# Boost_PWR_Supply.net
KiCad netlist of a schematic drawn in Altium Designer
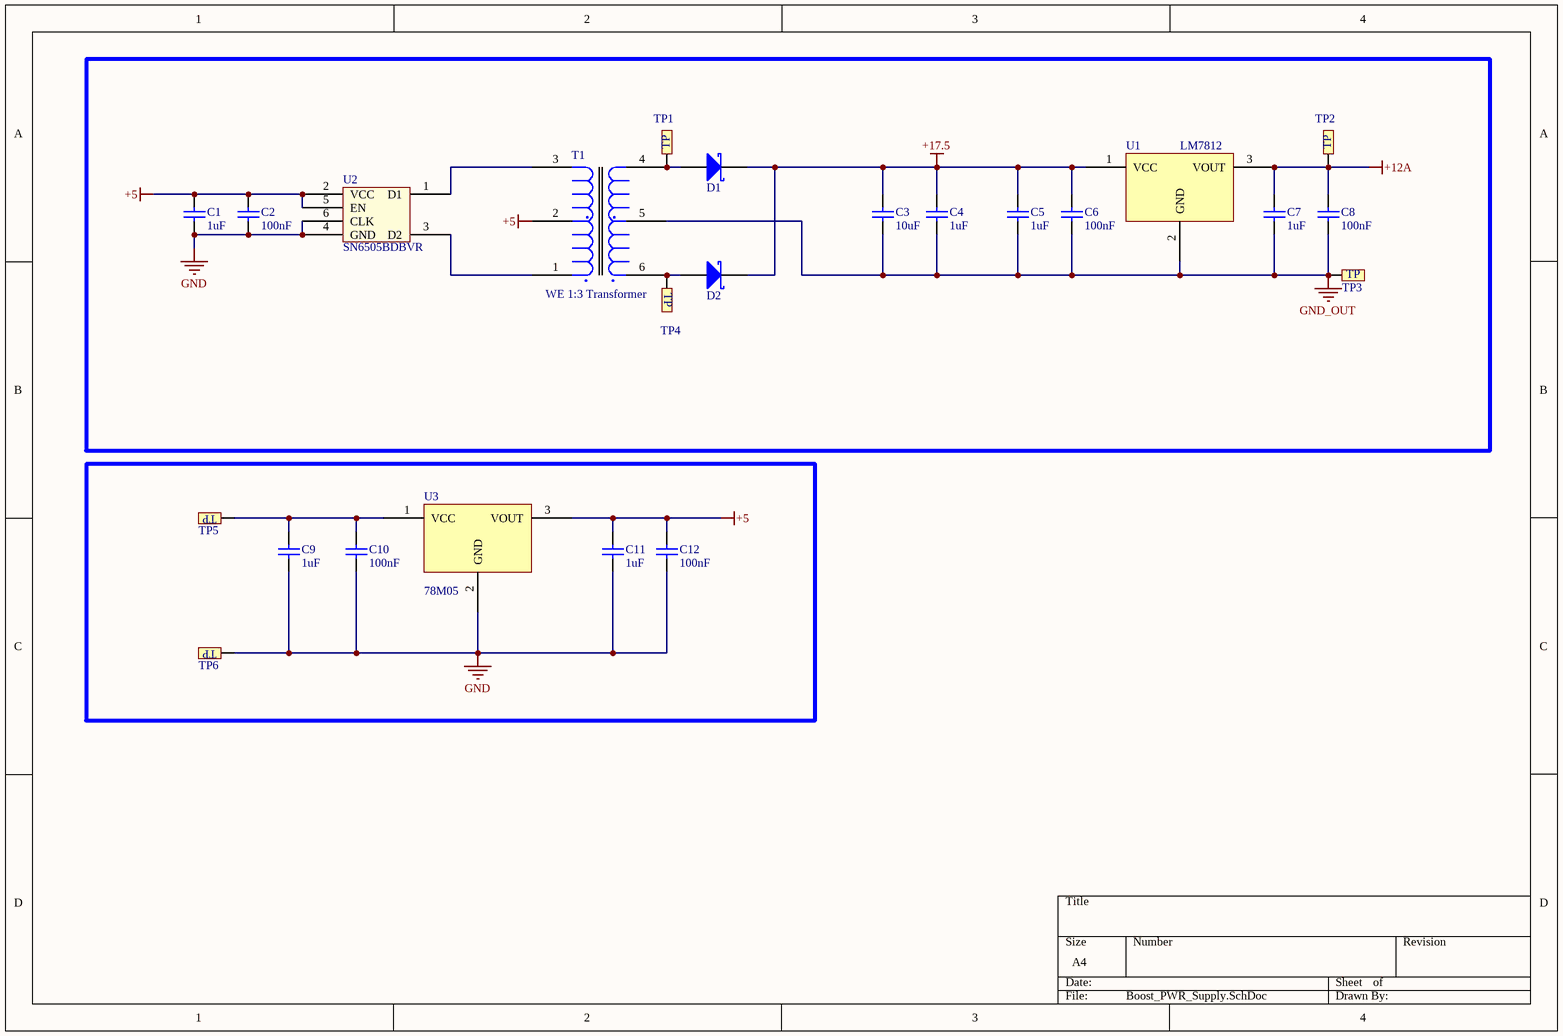
[diagram p0: Boost_PWR_Supply.SchDoc]

(export (version "E")
  (design (tool "Eeschema 10.0.6"))
  (components
    (comp (ref "C1")
      (value "1uF")
      (footprint "CAP-SM-0805")
      (description "Capacitor")
      (fields (field (name "Comment") "Cap Non-Pol SMD"))
      (libsource (lib "PIF_Library") (part "Cap Non-Pol SMD"))
    )
    (comp (ref "C2")
      (value "100nF")
      (footprint "CAP-SM-0805")
      (description "Capacitor")
      (fields (field (name "Comment") "Cap Non-Pol SMD"))
      (libsource (lib "PIF_Library") (part "Cap Non-Pol SMD"))
    )
    (comp (ref "C3")
      (value "10uF")
      (footprint "CAP-SM-0805")
      (description "Capacitor")
      (fields (field (name "Comment") "Cap Non-Pol SMD"))
      (libsource (lib "PIF_Library") (part "Cap Non-Pol SMD"))
    )
    (comp (ref "C4")
      (value "1uF")
      (footprint "CAP-SM-0805")
      (description "Capacitor")
      (fields (field (name "Comment") "Cap Non-Pol SMD"))
      (libsource (lib "PIF_Library") (part "Cap Non-Pol SMD"))
    )
    (comp (ref "C5")
      (value "1uF")
      (footprint "CAP-SM-0805")
      (description "Capacitor")
      (fields (field (name "Comment") "Cap Non-Pol SMD"))
      (libsource (lib "PIF_Library") (part "Cap Non-Pol SMD"))
    )
    (comp (ref "C6")
      (value "100nF")
      (footprint "CAP-SM-0805")
      (description "Capacitor")
      (fields (field (name "Comment") "Cap Non-Pol SMD"))
      (libsource (lib "PIF_Library") (part "Cap Non-Pol SMD"))
    )
    (comp (ref "C7")
      (value "1uF")
      (footprint "CAP-SM-0805")
      (description "Capacitor")
      (fields (field (name "Comment") "Cap Non-Pol SMD"))
      (libsource (lib "PIF_Library") (part "Cap Non-Pol SMD"))
    )
    (comp (ref "C8")
      (value "100nF")
      (footprint "CAP-SM-0805")
      (description "Capacitor")
      (fields (field (name "Comment") "Cap Non-Pol SMD"))
      (libsource (lib "PIF_Library") (part "Cap Non-Pol SMD"))
    )
    (comp (ref "C9")
      (value "1uF")
      (footprint "CAP-SM-0805")
      (description "Capacitor")
      (fields (field (name "Comment") "Cap Non-Pol SMD"))
      (libsource (lib "PIF_Library") (part "Cap Non-Pol SMD"))
    )
    (comp (ref "C10")
      (value "100nF")
      (footprint "CAP-SM-0805")
      (description "Capacitor")
      (fields (field (name "Comment") "Cap Non-Pol SMD"))
      (libsource (lib "PIF_Library") (part "Cap Non-Pol SMD"))
    )
    (comp (ref "C11")
      (value "1uF")
      (footprint "CAP-SM-0805")
      (description "Capacitor")
      (fields (field (name "Comment") "Cap Non-Pol SMD"))
      (libsource (lib "PIF_Library") (part "Cap Non-Pol SMD"))
    )
    (comp (ref "C12")
      (value "100nF")
      (footprint "CAP-SM-0805")
      (description "Capacitor")
      (fields (field (name "Comment") "Cap Non-Pol SMD"))
      (libsource (lib "PIF_Library") (part "Cap Non-Pol SMD"))
    )
    (comp (ref "D1")
      (value "D Schottky")
      (footprint "SS34")
      (description "Schottky Diode")
      (fields (field (name "PUBLISHER") "Altium Limited"))
      (libsource (lib "PIF_Library") (part "D Schottky"))
    )
    (comp (ref "D2")
      (value "D Schottky")
      (footprint "SS34")
      (description "Schottky Diode")
      (fields (field (name "PUBLISHER") "Altium Limited"))
      (libsource (lib "PIF_Library") (part "D Schottky"))
    )
    (comp (ref "T1")
      (value "WE 1:3 Transformer")
      (footprint "750316818")
      (fields (field (name "MANUFACTURER") "Wurth Elektronik"))
      (libsource (lib "MiclsLib") (part "WE 1{colon}3.5 Transformer"))
    )
    (comp (ref "TP1")
      (value "Test Point")
      (footprint "TP_2")
      (libsource (lib "PIF_Library") (part "Test Point"))
    )
    (comp (ref "TP2")
      (value "Test Point")
      (footprint "TP_2")
      (libsource (lib "PIF_Library") (part "Test Point"))
    )
    (comp (ref "TP3") (value "Test Point") (footprint "TP_2") (libsource (lib "") (part "Test Point_1")))
    (comp (ref "TP4") (value "Test Point") (footprint "TP_2") (libsource (lib "") (part "Test Point_3")))
    (comp (ref "TP5") (value "Test Point") (footprint "TP_2") (libsource (lib "") (part "Test Point_2")))
    (comp (ref "TP6") (value "Test Point") (footprint "TP_2") (libsource (lib "") (part "Test Point_2")))
    (comp (ref "U1")
      (value "LM7812")
      (footprint "DPAK228P1014X239-3N")
      (libsource (lib "MiclsLib") (part "LM78xx"))
    )
    (comp (ref "U2")
      (value "SN6505BDBVR")
      (footprint "SOT23-6")
      (description "IC TRANSFORMER DRIVER SOT23-6")
      (fields (field (name "MANUFACTURER") "Texas Instrument"))
      (libsource (lib "PIF_Lib") (part "SN6505BDBVR"))
    )
    (comp (ref "U3")
      (value "78M05")
      (footprint "DPAK228P1014X239-3N")
      (libsource (lib "IsolationBoostConverter") (part "LM78xx"))
    )
  )
  (nets
    (net (code "1") (name "+5") (class "Default")
      (node (ref "C1") (pin "2") (pinfunction "2_2") (pintype "passive"))
      (node (ref "C11") (pin "2") (pinfunction "2_2") (pintype "passive"))
      (node (ref "C12") (pin "2") (pinfunction "2_2") (pintype "passive"))
      (node (ref "C2") (pin "2") (pinfunction "2_2") (pintype "passive"))
      (node (ref "T1") (pin "2") (pinfunction "2_2") (pintype "passive"))
      (node (ref "U2") (pin "2") (pinfunction "VCC_2") (pintype "power_in"))
      (node (ref "U2") (pin "5") (pinfunction "EN_5") (pintype "passive"))
      (node (ref "U3") (pin "3") (pinfunction "VOUT_3") (pintype "passive"))
    )
    (net (code "2") (name "+12A") (class "Default")
      (node (ref "C7") (pin "2") (pinfunction "2_2") (pintype "passive"))
      (node (ref "C8") (pin "2") (pinfunction "2_2") (pintype "passive"))
      (node (ref "TP2") (pin "TP1") (pinfunction "0_TP1") (pintype "passive"))
      (node (ref "U1") (pin "3") (pinfunction "VOUT_3") (pintype "passive"))
    )
    (net (code "3") (name "+17.5") (class "Default")
      (node (ref "C3") (pin "2") (pinfunction "2_2") (pintype "passive"))
      (node (ref "C4") (pin "2") (pinfunction "2_2") (pintype "passive"))
      (node (ref "C5") (pin "2") (pinfunction "2_2") (pintype "passive"))
      (node (ref "C6") (pin "2") (pinfunction "2_2") (pintype "passive"))
      (node (ref "D1") (pin "2") (pinfunction "K_2") (pintype "passive"))
      (node (ref "D2") (pin "2") (pinfunction "K_2") (pintype "passive"))
      (node (ref "U1") (pin "1") (pinfunction "VCC_1") (pintype "passive"))
    )
    (net (code "4") (name "GND") (class "Default")
      (node (ref "C1") (pin "1") (pinfunction "1_1") (pintype "passive"))
      (node (ref "C10") (pin "1") (pinfunction "1_1") (pintype "passive"))
      (node (ref "C11") (pin "1") (pinfunction "1_1") (pintype "passive"))
      (node (ref "C12") (pin "1") (pinfunction "1_1") (pintype "passive"))
      (node (ref "C2") (pin "1") (pinfunction "1_1") (pintype "passive"))
      (node (ref "C9") (pin "1") (pinfunction "1_1") (pintype "passive"))
      (node (ref "TP6") (pin "TP1") (pinfunction "0_TP1") (pintype "passive"))
      (node (ref "U2") (pin "4") (pinfunction "GND_4") (pintype "power_in"))
      (node (ref "U2") (pin "6") (pinfunction "CLK_6") (pintype "passive"))
      (node (ref "U3") (pin "2") (pinfunction "GND_2") (pintype "passive"))
    )
    (net (code "5") (name "GND_OUT") (class "Default")
      (node (ref "C3") (pin "1") (pinfunction "1_1") (pintype "passive"))
      (node (ref "C4") (pin "1") (pinfunction "1_1") (pintype "passive"))
      (node (ref "C5") (pin "1") (pinfunction "1_1") (pintype "passive"))
      (node (ref "C6") (pin "1") (pinfunction "1_1") (pintype "passive"))
      (node (ref "C7") (pin "1") (pinfunction "1_1") (pintype "passive"))
      (node (ref "C8") (pin "1") (pinfunction "1_1") (pintype "passive"))
      (node (ref "T1") (pin "5") (pinfunction "5_5") (pintype "passive"))
      (node (ref "TP3") (pin "TP1") (pinfunction "0_TP1") (pintype "passive"))
      (node (ref "U1") (pin "2") (pinfunction "GND_2") (pintype "passive"))
    )
    (net (code "6") (name "Net-(D1-A)") (class "Default")
      (node (ref "D1") (pin "1") (pinfunction "A_1") (pintype "passive"))
      (node (ref "T1") (pin "4") (pinfunction "4_4") (pintype "passive"))
      (node (ref "TP1") (pin "TP1") (pinfunction "0_TP1") (pintype "passive"))
    )
    (net (code "7") (name "Net-(D2-A)") (class "Default")
      (node (ref "D2") (pin "1") (pinfunction "A_1") (pintype "passive"))
      (node (ref "T1") (pin "6") (pinfunction "6_6") (pintype "passive"))
      (node (ref "TP4") (pin "TP1") (pinfunction "0_TP1") (pintype "passive"))
    )
    (net (code "8") (name "Net-(TP5-0)") (class "Default")
      (node (ref "C10") (pin "2") (pinfunction "2_2") (pintype "passive"))
      (node (ref "C9") (pin "2") (pinfunction "2_2") (pintype "passive"))
      (node (ref "TP5") (pin "TP1") (pinfunction "0_TP1") (pintype "passive"))
      (node (ref "U3") (pin "1") (pinfunction "VCC_1") (pintype "passive"))
    )
    (net (code "9") (name "Net-(U2-D1)") (class "Default")
      (node (ref "T1") (pin "3") (pinfunction "3_3") (pintype "passive"))
      (node (ref "U2") (pin "1") (pinfunction "D1_1") (pintype "passive"))
    )
    (net (code "10") (name "Net-(U2-D2)") (class "Default")
      (node (ref "T1") (pin "1") (pinfunction "1_1") (pintype "passive"))
      (node (ref "U2") (pin "3") (pinfunction "D2_3") (pintype "passive"))
    )
  )
)
